# PETDOG-2.net
KiCad netlist of a schematic drawn in EAGLE
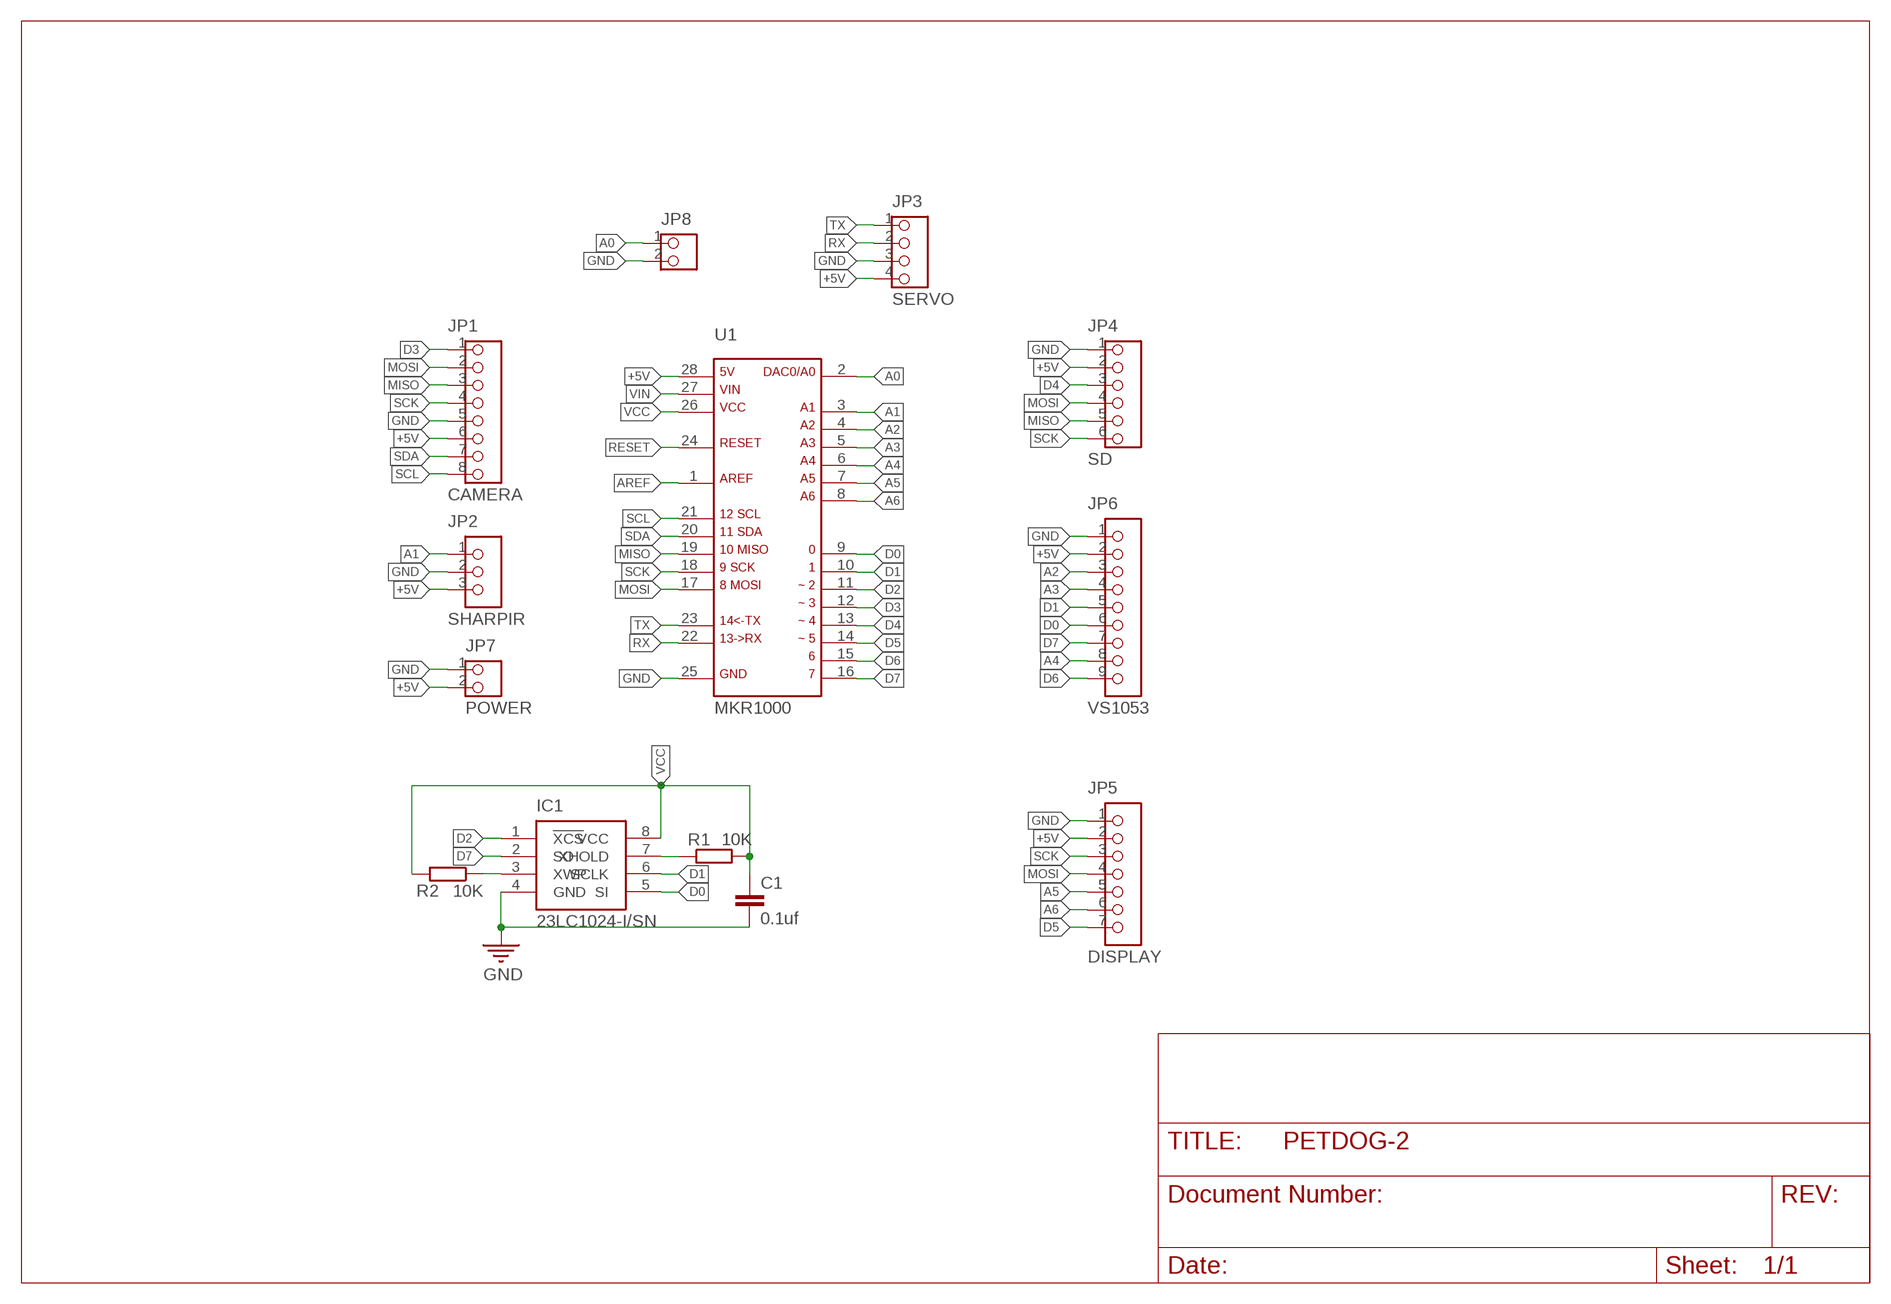
[diagram p0: schematic, sheet 1]

(export (version "E")
  (design (tool "Eeschema 10.0.6"))
  (components
    (comp (ref "C1")
      (value "0.1uf")
      (footprint "eagle-import:C0603")
      (libsource (lib "eagle-import") (part "C-EUC0603"))
    )
    (comp (ref "IC1")
      (value "23LC1024-I/SN")
      (footprint "eagle-import:VS23S010C-S")
      (libsource (lib "eagle-import") (part "VS23S010C-S"))
    )
    (comp (ref "JP1")
      (value "CAMERA")
      (footprint "eagle-import:PIN-1X8")
      (libsource (lib "eagle-import") (part "PIN-1X8"))
    )
    (comp (ref "JP2")
      (value "SHARPIR")
      (footprint "eagle-import:PIN-1X3")
      (libsource (lib "eagle-import") (part "PIN-1X3"))
    )
    (comp (ref "JP3")
      (value "SERVO")
      (footprint "eagle-import:PIN-1X4")
      (libsource (lib "eagle-import") (part "PIN-1X4"))
    )
    (comp (ref "JP4")
      (value "SD")
      (footprint "eagle-import:PIN-1X6")
      (libsource (lib "eagle-import") (part "PIN-1X6"))
    )
    (comp (ref "JP5")
      (value "DISPLAY")
      (footprint "eagle-import:PIN-1X7")
      (libsource (lib "eagle-import") (part "PIN-1X7"))
    )
    (comp (ref "JP6")
      (value "VS1053")
      (footprint "eagle-import:PIN-1X9")
      (libsource (lib "eagle-import") (part "PIN-1X9"))
    )
    (comp (ref "JP7")
      (value "POWER")
      (footprint "eagle-import:PIN-1X2")
      (libsource (lib "eagle-import") (part "PIN-1X2"))
    )
    (comp (ref "JP8")
      (value "PAM8403")
      (footprint "eagle-import:PIN-1X2")
      (libsource (lib "eagle-import") (part "PIN-1X2"))
    )
    (comp (ref "R1")
      (value "10K")
      (footprint "eagle-import:R0603")
      (libsource (lib "eagle-import") (part "R-EU_R0603"))
    )
    (comp (ref "R2")
      (value "10K")
      (footprint "eagle-import:R0603")
      (libsource (lib "eagle-import") (part "R-EU_R0603"))
    )
    (comp (ref "U1")
      (value "MKR1000")
      (footprint "eagle-import:MKR1000-2")
      (libsource (lib "eagle-import") (part "MKR1000-2"))
    )
  )
  (nets
    (net (code "1") (name "+5V") (class "Default")
      (node (ref "JP1") (pin "6") (pinfunction "P$6_6") (pintype "passive"))
      (node (ref "JP2") (pin "3") (pinfunction "AIN_3") (pintype "passive"))
      (node (ref "JP3") (pin "4") (pinfunction "GND_4") (pintype "passive"))
      (node (ref "JP4") (pin "2") (pinfunction "$2_2") (pintype "passive"))
      (node (ref "JP5") (pin "2") (pinfunction "P$2_2") (pintype "passive"))
      (node (ref "JP6") (pin "2") (pinfunction "P$2_2") (pintype "passive"))
      (node (ref "JP7") (pin "2") (pinfunction "P$2_2") (pintype "passive"))
      (node (ref "U1") (pin "28") (pinfunction "5V_28") (pintype "power_in"))
    )
    (net (code "2") (name "A0") (class "Default")
      (node (ref "JP8") (pin "1") (pinfunction "P$1_1") (pintype "passive"))
      (node (ref "U1") (pin "2") (pinfunction "DAC0/A0_2") (pintype "bidirectional"))
    )
    (net (code "3") (name "A1") (class "Default")
      (node (ref "JP2") (pin "1") (pinfunction "GND_1") (pintype "passive"))
      (node (ref "U1") (pin "3") (pinfunction "A1_3") (pintype "output"))
    )
    (net (code "4") (name "A2") (class "Default")
      (node (ref "JP6") (pin "3") (pinfunction "P$3_3") (pintype "passive"))
      (node (ref "U1") (pin "4") (pinfunction "A2_4") (pintype "output"))
    )
    (net (code "5") (name "A3") (class "Default")
      (node (ref "JP6") (pin "4") (pinfunction "P$4_4") (pintype "passive"))
      (node (ref "U1") (pin "5") (pinfunction "A3_5") (pintype "output"))
    )
    (net (code "6") (name "A4") (class "Default")
      (node (ref "JP6") (pin "8") (pinfunction "P$8_8") (pintype "passive"))
      (node (ref "U1") (pin "6") (pinfunction "A4_6") (pintype "output"))
    )
    (net (code "7") (name "A5") (class "Default")
      (node (ref "JP5") (pin "5") (pinfunction "P$5_5") (pintype "passive"))
      (node (ref "U1") (pin "7") (pinfunction "A5_7") (pintype "output"))
    )
    (net (code "8") (name "A6") (class "Default")
      (node (ref "JP5") (pin "6") (pinfunction "P$6_6") (pintype "passive"))
      (node (ref "U1") (pin "8") (pinfunction "A6_8") (pintype "output"))
    )
    (net (code "9") (name "AREF") (class "Default")
      (node (ref "U1") (pin "1") (pinfunction "AREF_1") (pintype "bidirectional"))
    )
    (net (code "10") (name "D0") (class "Default")
      (node (ref "IC1") (pin "5") (pinfunction "SI_5") (pintype "bidirectional"))
      (node (ref "JP6") (pin "6") (pinfunction "P$6_6") (pintype "passive"))
      (node (ref "U1") (pin "9") (pinfunction "0_9") (pintype "bidirectional"))
    )
    (net (code "11") (name "D1") (class "Default")
      (node (ref "IC1") (pin "6") (pinfunction "SCLK_6") (pintype "output"))
      (node (ref "JP6") (pin "5") (pinfunction "P$5_5") (pintype "passive"))
      (node (ref "U1") (pin "10") (pinfunction "1_10") (pintype "bidirectional"))
    )
    (net (code "12") (name "D2") (class "Default")
      (node (ref "IC1") (pin "1") (pinfunction "~{XCS}_1") (pintype "input"))
      (node (ref "U1") (pin "11") (pinfunction "~{2}_11") (pintype "bidirectional"))
    )
    (net (code "13") (name "D3") (class "Default")
      (node (ref "JP1") (pin "1") (pinfunction "P$1_1") (pintype "passive"))
      (node (ref "U1") (pin "12") (pinfunction "~{3}_12") (pintype "bidirectional"))
    )
    (net (code "14") (name "D4") (class "Default")
      (node (ref "JP4") (pin "3") (pinfunction "$3_3") (pintype "passive"))
      (node (ref "U1") (pin "13") (pinfunction "~{4}_13") (pintype "bidirectional"))
    )
    (net (code "15") (name "D5") (class "Default")
      (node (ref "JP5") (pin "7") (pinfunction "P$7_7") (pintype "passive"))
      (node (ref "U1") (pin "14") (pinfunction "~{5}_14") (pintype "bidirectional"))
    )
    (net (code "16") (name "D6") (class "Default")
      (node (ref "JP6") (pin "9") (pinfunction "P$9_9") (pintype "passive"))
      (node (ref "U1") (pin "15") (pinfunction "6_15") (pintype "bidirectional"))
    )
    (net (code "17") (name "D7") (class "Default")
      (node (ref "IC1") (pin "2") (pinfunction "SO_2") (pintype "bidirectional"))
      (node (ref "JP6") (pin "7") (pinfunction "P$7_7") (pintype "passive"))
      (node (ref "U1") (pin "16") (pinfunction "7_16") (pintype "bidirectional"))
    )
    (net (code "18") (name "GND") (class "Default")
      (node (ref "C1") (pin "2") (pinfunction "2_2") (pintype "passive"))
      (node (ref "IC1") (pin "4") (pinfunction "GND_4") (pintype "power_in"))
      (node (ref "JP1") (pin "5") (pinfunction "P$5_5") (pintype "passive"))
      (node (ref "JP2") (pin "2") (pinfunction "VCC_2") (pintype "passive"))
      (node (ref "JP3") (pin "3") (pinfunction "VCC_3") (pintype "passive"))
      (node (ref "JP4") (pin "1") (pinfunction "$1_1") (pintype "passive"))
      (node (ref "JP5") (pin "1") (pinfunction "P$1_1") (pintype "passive"))
      (node (ref "JP6") (pin "1") (pinfunction "P$1_1") (pintype "passive"))
      (node (ref "JP7") (pin "1") (pinfunction "P$1_1") (pintype "passive"))
      (node (ref "JP8") (pin "2") (pinfunction "P$2_2") (pintype "passive"))
      (node (ref "U1") (pin "25") (pinfunction "GND_25") (pintype "power_in"))
    )
    (net (code "19") (name "MISO") (class "Default")
      (node (ref "JP1") (pin "3") (pinfunction "P$3_3") (pintype "passive"))
      (node (ref "JP4") (pin "5") (pinfunction "$5_5") (pintype "passive"))
      (node (ref "U1") (pin "19") (pinfunction "MISO_19") (pintype "input"))
    )
    (net (code "20") (name "MOSI") (class "Default")
      (node (ref "JP1") (pin "2") (pinfunction "P$2_2") (pintype "passive"))
      (node (ref "JP4") (pin "4") (pinfunction "$4_4") (pintype "passive"))
      (node (ref "JP5") (pin "4") (pinfunction "P$4_4") (pintype "passive"))
      (node (ref "U1") (pin "17") (pinfunction "MOSI_17") (pintype "output"))
    )
    (net (code "21") (name "Net-(IC1-XHOLD)") (class "Default")
      (node (ref "IC1") (pin "7") (pinfunction "XHOLD_7") (pintype "bidirectional"))
      (node (ref "R1") (pin "1") (pinfunction "1_1") (pintype "passive"))
    )
    (net (code "22") (name "Net-(IC1-XWP)") (class "Default")
      (node (ref "IC1") (pin "3") (pinfunction "XWP_3") (pintype "bidirectional"))
      (node (ref "R2") (pin "1") (pinfunction "1_1") (pintype "passive"))
    )
    (net (code "23") (name "RESET") (class "Default")
      (node (ref "U1") (pin "24") (pinfunction "RESET_24") (pintype "power_in"))
    )
    (net (code "24") (name "RX") (class "Default")
      (node (ref "JP3") (pin "2") (pinfunction "IO2_2") (pintype "passive"))
      (node (ref "U1") (pin "22") (pinfunction "RX_22") (pintype "input"))
    )
    (net (code "25") (name "SCK") (class "Default")
      (node (ref "JP1") (pin "4") (pinfunction "P$4_4") (pintype "passive"))
      (node (ref "JP4") (pin "6") (pinfunction "$6_6") (pintype "passive"))
      (node (ref "JP5") (pin "3") (pinfunction "P$3_3") (pintype "passive"))
      (node (ref "U1") (pin "18") (pinfunction "SCK_18") (pintype "output"))
    )
    (net (code "26") (name "SCL") (class "Default")
      (node (ref "JP1") (pin "8") (pinfunction "P$8_8") (pintype "passive"))
      (node (ref "U1") (pin "21") (pinfunction "SCL_21") (pintype "output"))
    )
    (net (code "27") (name "SDA") (class "Default")
      (node (ref "JP1") (pin "7") (pinfunction "P$7_7") (pintype "passive"))
      (node (ref "U1") (pin "20") (pinfunction "SDA_20") (pintype "bidirectional"))
    )
    (net (code "28") (name "TX") (class "Default")
      (node (ref "JP3") (pin "1") (pinfunction "IO1_1") (pintype "passive"))
      (node (ref "U1") (pin "23") (pinfunction "TX_23") (pintype "output"))
    )
    (net (code "29") (name "VCC") (class "Default")
      (node (ref "C1") (pin "1") (pinfunction "1_1") (pintype "passive"))
      (node (ref "IC1") (pin "8") (pinfunction "VCC_8") (pintype "power_in"))
      (node (ref "R1") (pin "2") (pinfunction "2_2") (pintype "passive"))
      (node (ref "R2") (pin "2") (pinfunction "2_2") (pintype "passive"))
      (node (ref "U1") (pin "26") (pinfunction "VCC_26") (pintype "power_in"))
    )
    (net (code "30") (name "VIN") (class "Default")
      (node (ref "U1") (pin "27") (pinfunction "VIN_27") (pintype "power_in"))
    )
  )
)
